# powerStageC_rev1.net
KiCad netlist of a schematic drawn in EAGLE
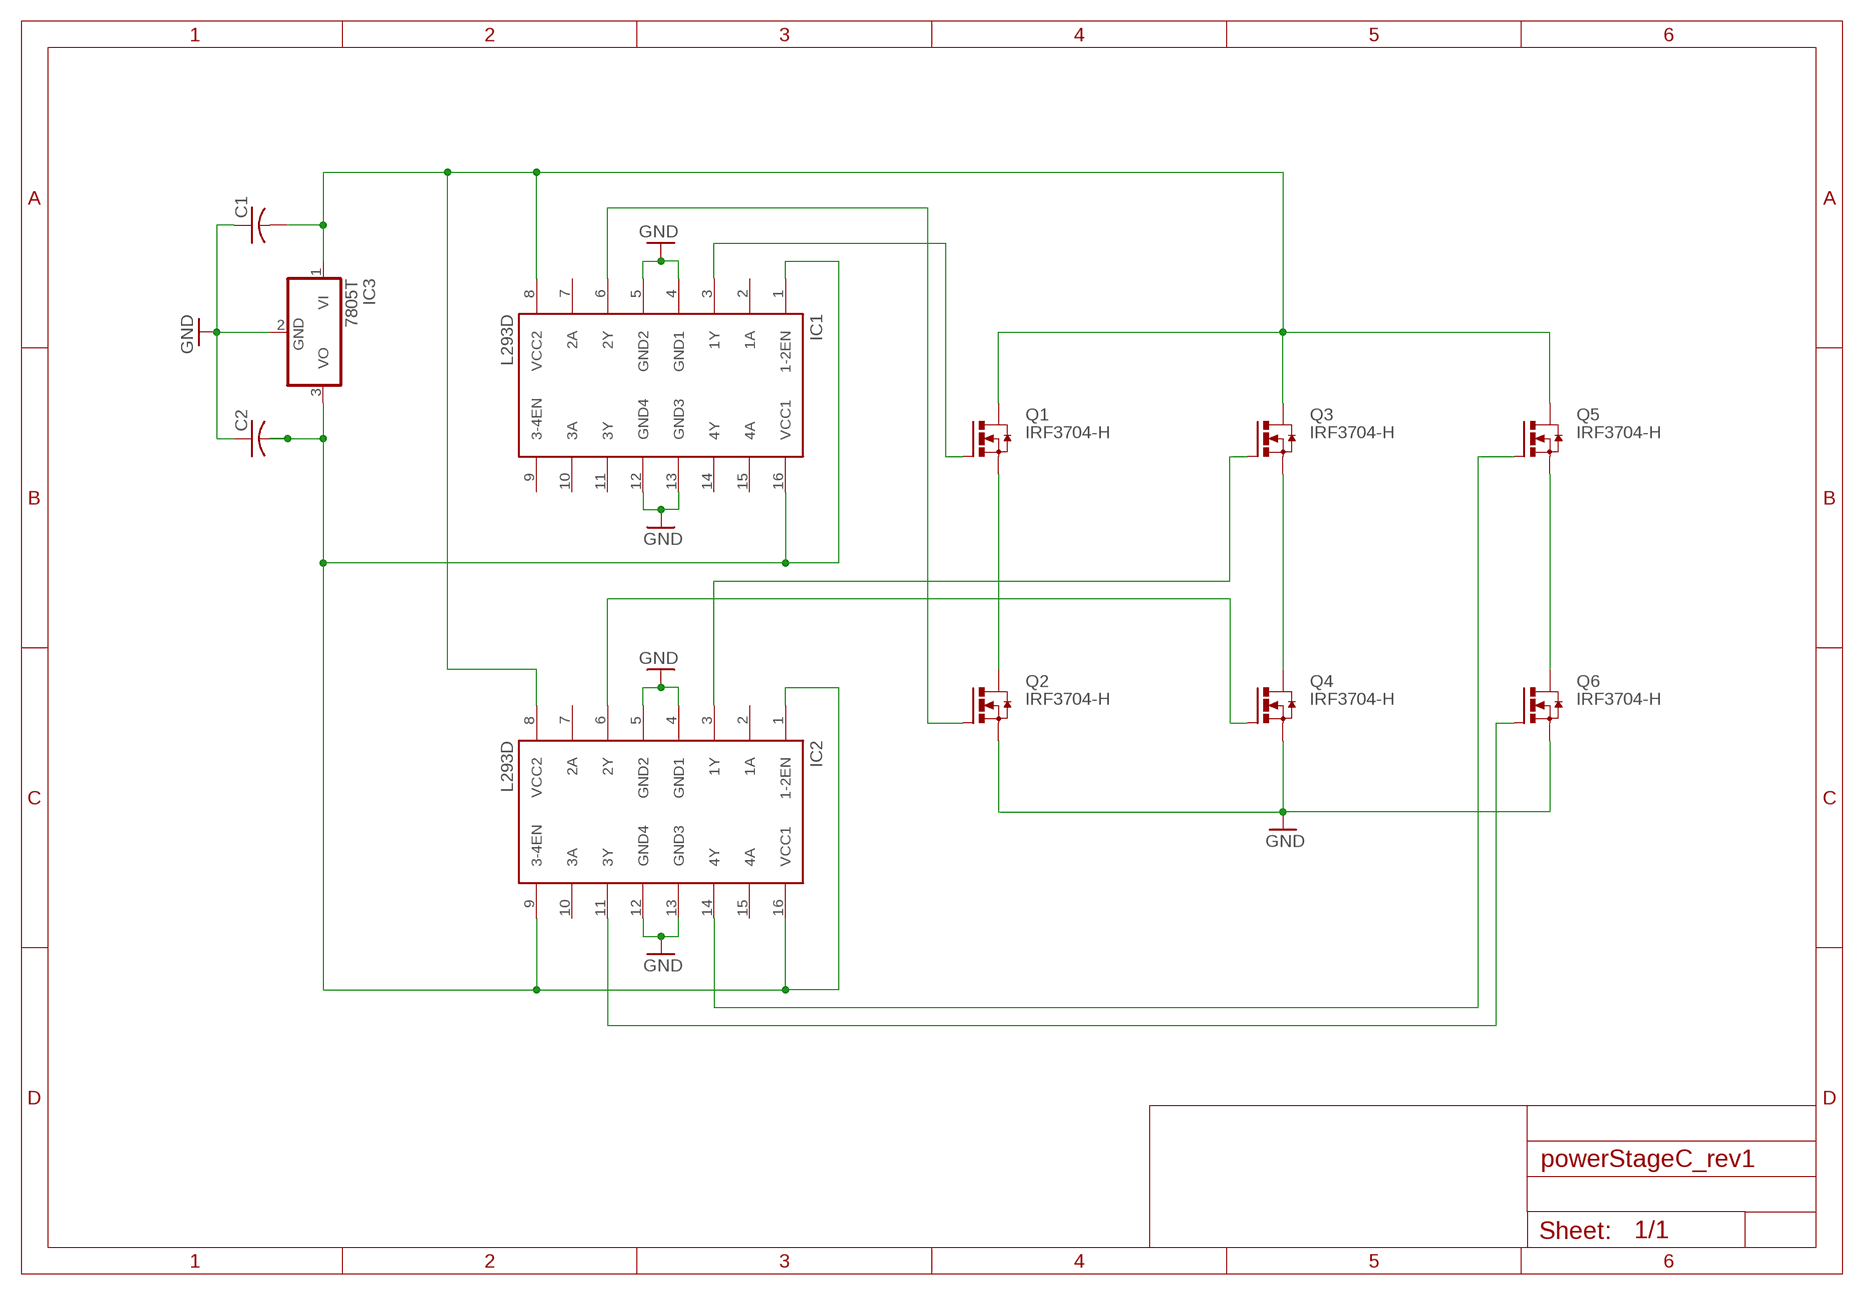
[diagram p0: schematic, sheet 1]

(export (version "E")
  (design (tool "Eeschema 10.0.6"))
  (components
    (comp (ref "C1")
      (value "C-US025_050-025X075")
      (footprint "eagle-import:C025_050-025X075")
      (libsource (lib "eagle-import") (part "C-US025_050-025X075"))
    )
    (comp (ref "C2")
      (value "C-US025_050-025X075")
      (footprint "eagle-import:C025_050-025X075")
      (libsource (lib "eagle-import") (part "C-US025_050-025X075"))
    )
    (comp (ref "IC1")
      (value "L293D")
      (footprint "eagle-import:DIL16")
      (libsource (lib "eagle-import") (part "L293D"))
    )
    (comp (ref "IC2")
      (value "L293D")
      (footprint "eagle-import:DIL16")
      (libsource (lib "eagle-import") (part "L293D"))
    )
    (comp (ref "IC3")
      (value "7805T")
      (footprint "eagle-import:TO220H")
      (libsource (lib "eagle-import") (part "78T05"))
    )
    (comp (ref "Q1")
      (value "IRF3704-H")
      (footprint "eagle-import:TO220BH")
      (libsource (lib "eagle-import") (part "IRF3704-H"))
    )
    (comp (ref "Q2")
      (value "IRF3704-H")
      (footprint "eagle-import:TO220BH")
      (libsource (lib "eagle-import") (part "IRF3704-H"))
    )
    (comp (ref "Q3")
      (value "IRF3704-H")
      (footprint "eagle-import:TO220BH")
      (libsource (lib "eagle-import") (part "IRF3704-H"))
    )
    (comp (ref "Q4")
      (value "IRF3704-H")
      (footprint "eagle-import:TO220BH")
      (libsource (lib "eagle-import") (part "IRF3704-H"))
    )
    (comp (ref "Q5")
      (value "IRF3704-H")
      (footprint "eagle-import:TO220BH")
      (libsource (lib "eagle-import") (part "IRF3704-H"))
    )
    (comp (ref "Q6")
      (value "IRF3704-H")
      (footprint "eagle-import:TO220BH")
      (libsource (lib "eagle-import") (part "IRF3704-H"))
    )
  )
  (nets
    (net (code "1") (name "GND") (class "Default")
      (node (ref "C1") (pin "1") (pinfunction "1_1") (pintype "passive"))
      (node (ref "C2") (pin "1") (pinfunction "1_1") (pintype "passive"))
      (node (ref "IC1") (pin "12") (pinfunction "GND4_12") (pintype "power_in"))
      (node (ref "IC1") (pin "13") (pinfunction "GND3_13") (pintype "power_in"))
      (node (ref "IC1") (pin "4") (pinfunction "GND1_4") (pintype "power_in"))
      (node (ref "IC1") (pin "5") (pinfunction "GND2_5") (pintype "power_in"))
      (node (ref "IC2") (pin "12") (pinfunction "GND4_12") (pintype "power_in"))
      (node (ref "IC2") (pin "13") (pinfunction "GND3_13") (pintype "power_in"))
      (node (ref "IC2") (pin "4") (pinfunction "GND1_4") (pintype "power_in"))
      (node (ref "IC2") (pin "5") (pinfunction "GND2_5") (pintype "power_in"))
      (node (ref "IC3") (pin "2") (pinfunction "GND_2") (pintype "passive"))
      (node (ref "Q2") (pin "S") (pinfunction "S_S") (pintype "passive"))
      (node (ref "Q4") (pin "S") (pinfunction "S_S") (pintype "passive"))
      (node (ref "Q6") (pin "S") (pinfunction "S_S") (pintype "passive"))
    )
    (net (code "2") (name "Net-(IC1-1-2EN)") (class "Default")
      (node (ref "C2") (pin "2") (pinfunction "2_2") (pintype "passive"))
      (node (ref "IC1") (pin "1") (pinfunction "1-2EN_1") (pintype "input"))
      (node (ref "IC1") (pin "16") (pinfunction "VCC1_16") (pintype "power_in"))
      (node (ref "IC2") (pin "1") (pinfunction "1-2EN_1") (pintype "input"))
      (node (ref "IC2") (pin "16") (pinfunction "VCC1_16") (pintype "power_in"))
      (node (ref "IC2") (pin "9") (pinfunction "3-4EN_9") (pintype "input"))
      (node (ref "IC3") (pin "3") (pinfunction "VO_3") (pintype "passive"))
    )
    (net (code "3") (name "Net-(IC1-1Y)") (class "Default")
      (node (ref "IC1") (pin "3") (pinfunction "1Y_3") (pintype "output"))
      (node (ref "Q1") (pin "G") (pinfunction "G_G") (pintype "passive"))
    )
    (net (code "4") (name "Net-(IC1-2Y)") (class "Default")
      (node (ref "IC1") (pin "6") (pinfunction "2Y_6") (pintype "output"))
      (node (ref "Q2") (pin "G") (pinfunction "G_G") (pintype "passive"))
    )
    (net (code "5") (name "Net-(IC1-VCC2)") (class "Default")
      (node (ref "C1") (pin "2") (pinfunction "2_2") (pintype "passive"))
      (node (ref "IC1") (pin "8") (pinfunction "VCC2_8") (pintype "power_in"))
      (node (ref "IC2") (pin "8") (pinfunction "VCC2_8") (pintype "power_in"))
      (node (ref "IC3") (pin "1") (pinfunction "VI_1") (pintype "input"))
      (node (ref "Q1") (pin "D") (pinfunction "D_D") (pintype "passive"))
      (node (ref "Q3") (pin "D") (pinfunction "D_D") (pintype "passive"))
      (node (ref "Q5") (pin "D") (pinfunction "D_D") (pintype "passive"))
    )
    (net (code "6") (name "Net-(IC2-1Y)") (class "Default")
      (node (ref "IC2") (pin "3") (pinfunction "1Y_3") (pintype "output"))
      (node (ref "Q3") (pin "G") (pinfunction "G_G") (pintype "passive"))
    )
    (net (code "7") (name "Net-(IC2-2Y)") (class "Default")
      (node (ref "IC2") (pin "6") (pinfunction "2Y_6") (pintype "output"))
      (node (ref "Q4") (pin "G") (pinfunction "G_G") (pintype "passive"))
    )
    (net (code "8") (name "Net-(IC2-3Y)") (class "Default")
      (node (ref "IC2") (pin "11") (pinfunction "3Y_11") (pintype "output"))
      (node (ref "Q6") (pin "G") (pinfunction "G_G") (pintype "passive"))
    )
    (net (code "9") (name "Net-(IC2-4Y)") (class "Default")
      (node (ref "IC2") (pin "14") (pinfunction "4Y_14") (pintype "output"))
      (node (ref "Q5") (pin "G") (pinfunction "G_G") (pintype "passive"))
    )
    (net (code "10") (name "Net-(Q1-PadS)") (class "Default")
      (node (ref "Q1") (pin "S") (pinfunction "S_S") (pintype "passive"))
      (node (ref "Q2") (pin "D") (pinfunction "D_D") (pintype "passive"))
    )
    (net (code "11") (name "Net-(Q3-PadS)") (class "Default")
      (node (ref "Q3") (pin "S") (pinfunction "S_S") (pintype "passive"))
      (node (ref "Q4") (pin "D") (pinfunction "D_D") (pintype "passive"))
    )
    (net (code "12") (name "Net-(Q5-PadS)") (class "Default")
      (node (ref "Q5") (pin "S") (pinfunction "S_S") (pintype "passive"))
      (node (ref "Q6") (pin "D") (pinfunction "D_D") (pintype "passive"))
    )
    (net (code "13") (name "unconnected-(IC1-1A-Pad2)") (class "Default")
      (node (ref "IC1") (pin "2") (pinfunction "1A_2") (pintype "input"))
    )
    (net (code "14") (name "unconnected-(IC1-2A-Pad7)") (class "Default")
      (node (ref "IC1") (pin "7") (pinfunction "2A_7") (pintype "input"))
    )
    (net (code "15") (name "unconnected-(IC1-3-4EN-Pad9)") (class "Default")
      (node (ref "IC1") (pin "9") (pinfunction "3-4EN_9") (pintype "input"))
    )
    (net (code "16") (name "unconnected-(IC1-3A-Pad10)") (class "Default")
      (node (ref "IC1") (pin "10") (pinfunction "3A_10") (pintype "input"))
    )
    (net (code "17") (name "unconnected-(IC1-3Y-Pad11)") (class "Default")
      (node (ref "IC1") (pin "11") (pinfunction "3Y_11") (pintype "output"))
    )
    (net (code "18") (name "unconnected-(IC1-4A-Pad15)") (class "Default")
      (node (ref "IC1") (pin "15") (pinfunction "4A_15") (pintype "input"))
    )
    (net (code "19") (name "unconnected-(IC1-4Y-Pad14)") (class "Default")
      (node (ref "IC1") (pin "14") (pinfunction "4Y_14") (pintype "output"))
    )
    (net (code "20") (name "unconnected-(IC2-1A-Pad2)") (class "Default")
      (node (ref "IC2") (pin "2") (pinfunction "1A_2") (pintype "input"))
    )
    (net (code "21") (name "unconnected-(IC2-2A-Pad7)") (class "Default")
      (node (ref "IC2") (pin "7") (pinfunction "2A_7") (pintype "input"))
    )
    (net (code "22") (name "unconnected-(IC2-3A-Pad10)") (class "Default")
      (node (ref "IC2") (pin "10") (pinfunction "3A_10") (pintype "input"))
    )
    (net (code "23") (name "unconnected-(IC2-4A-Pad15)") (class "Default")
      (node (ref "IC2") (pin "15") (pinfunction "4A_15") (pintype "input"))
    )
  )
)
